# SWR_Tandem_Match.net
KiCad netlist of a schematic drawn in Altium Designer
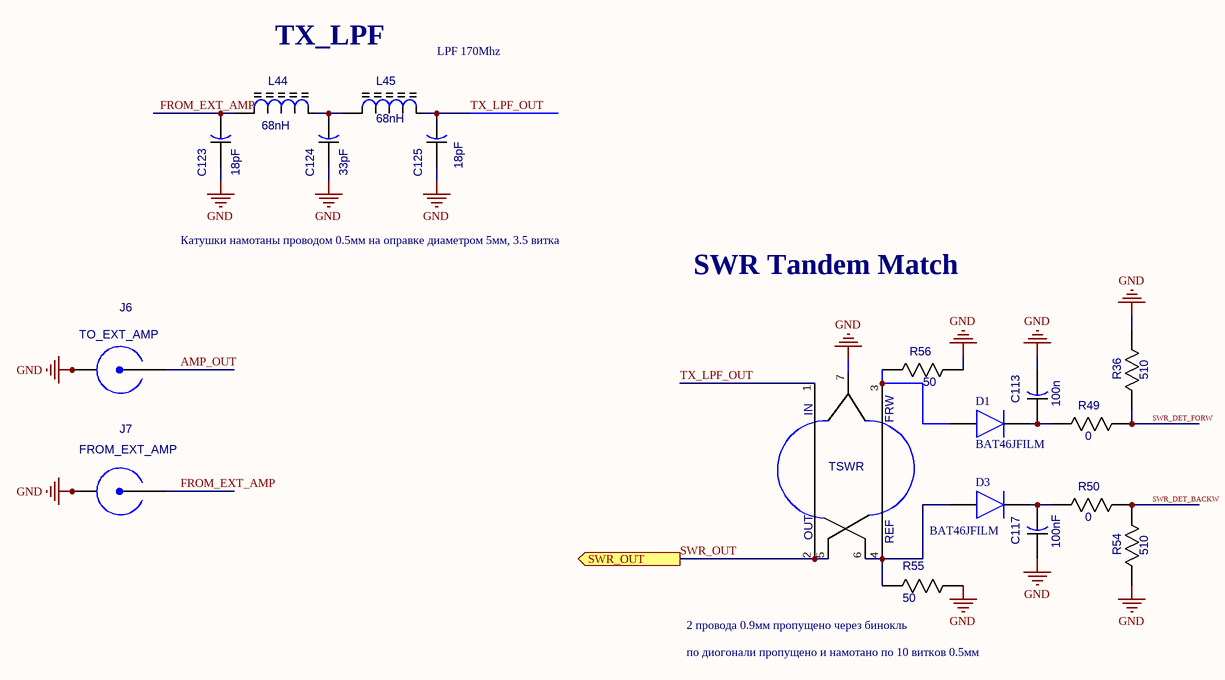
[diagram p0: SWR Tandem Match.SchDoc]

(export (version "E")
  (design (tool "Eeschema 10.0.6"))
  (components
    (comp (ref "C113")
      (value "100n")
      (footprint "CAP_0805")
      (description "CAP_0805")
      (libsource (lib "*") (part "CAP_0805"))
    )
    (comp (ref "C117")
      (value "100nF")
      (footprint "CAP_0805")
      (description "CAP_0805")
      (libsource (lib "*") (part "CAP_0805"))
    )
    (comp (ref "C123")
      (value "18pF")
      (footprint "CAP_1206")
      (description "CAP_1206")
      (libsource (lib "*") (part "CAP_1206"))
    )
    (comp (ref "C124")
      (value "33pF")
      (footprint "CAP_1206")
      (description "CAP_1206")
      (libsource (lib "*") (part "CAP_1206"))
    )
    (comp (ref "C125")
      (value "18pF")
      (footprint "CAP_1206")
      (description "CAP_1206")
      (libsource (lib "*") (part "CAP_1206"))
    )
    (comp (ref "D1")
      (value "BAT46JFILM")
      (footprint "SamacSys:SOD2513X117N")
      (description "Diode")
      (fields (field (name "MOUSER PART NUMBER") "511-BAT46JFILM") (field (name "RS PART NUMBER") "7146847P"))
      (libsource (lib "*") (part "BAT46JFILM"))
    )
    (comp (ref "D3")
      (value "BAT46JFILM")
      (footprint "SamacSys:SOD2513X117N")
      (description "Diode")
      (fields (field (name "MOUSER PART NUMBER") "511-BAT46JFILM") (field (name "RS PART NUMBER") "7146847P"))
      (libsource (lib "*") (part "BAT46JFILM"))
    )
    (comp (ref "J6")
      (value "TO_EXT_AMP")
      (footprint "31-5431")
      (description "SMA")
      (libsource (lib "RF-UNIT_1") (part "31-5431"))
    )
    (comp (ref "J7")
      (value "FROM_EXT_AMP")
      (footprint "31-5431")
      (description "SMA")
      (libsource (lib "RF-UNIT_1") (part "31-5431"))
    )
    (comp (ref "L44")
      (value "68nH")
      (footprint "IND_FERRITE_CORE_1")
      (description "Inductor")
      (libsource (lib "*") (part "IND_FERRITE_CORE"))
    )
    (comp (ref "L45")
      (value "68nH")
      (footprint "IND_FERRITE_CORE_1")
      (description "Inductor")
      (libsource (lib "*") (part "IND_FERRITE_CORE"))
    )
    (comp (ref "R36")
      (value "510")
      (footprint "RES_0805")
      (description "RES_0805")
      (libsource (lib "*") (part "RES_0805"))
    )
    (comp (ref "R49")
      (value "0")
      (footprint "RES_0805")
      (description "RES_0805")
      (libsource (lib "*") (part "RES_0805"))
    )
    (comp (ref "R50")
      (value "0")
      (footprint "RES_0805")
      (description "RES_0805")
      (libsource (lib "*") (part "RES_0805"))
    )
    (comp (ref "R54")
      (value "510")
      (footprint "RES_0805")
      (description "RES_0805")
      (libsource (lib "*") (part "RES_0805"))
    )
    (comp (ref "R55")
      (value "50")
      (footprint "RES_1206")
      (description "RES_1206")
      (libsource (lib "*") (part "RES_1206"))
    )
    (comp (ref "R56")
      (value "50")
      (footprint "RES_1206")
      (description "RES_1206")
      (libsource (lib "*") (part "RES_1206"))
    )
    (comp (ref "TSWR")
      (value "SWR_TANDEM_MATCH")
      (footprint "SWR_TANDEM_MATCH")
      (libsource (lib "*") (part "SWR_TANDEM_MATCH"))
    )
  )
  (nets
    (net (code "1") (name "/AMP_OUT") (class "Default")
      (node (ref "J6") (pin "5") (pinfunction "CON_5") (pintype "passive"))
    )
    (net (code "2") (name "/FROM_EXT_AMP") (class "Default")
      (node (ref "C123") (pin "2") (pinfunction "2_2") (pintype "passive"))
      (node (ref "J7") (pin "5") (pinfunction "CON_5") (pintype "passive"))
      (node (ref "L44") (pin "1") (pinfunction "A_1") (pintype "passive"))
    )
    (net (code "3") (name "/SWR_DET_BACKW") (class "Default")
      (node (ref "R50") (pin "2") (pinfunction "2_2") (pintype "passive"))
      (node (ref "R54") (pin "2") (pinfunction "2_2") (pintype "passive"))
    )
    (net (code "4") (name "/SWR_DET_FORW") (class "Default")
      (node (ref "R36") (pin "1") (pinfunction "1_1") (pintype "passive"))
      (node (ref "R49") (pin "2") (pinfunction "2_2") (pintype "passive"))
    )
    (net (code "5") (name "/SWR_OUT") (class "Default")
      (node (ref "TSWR") (pin "2") (pinfunction "2_2") (pintype "passive"))
      (node (ref "TSWR") (pin "5") (pinfunction "5_5") (pintype "passive"))
    )
    (net (code "6") (name "/TX_LPF_OUT") (class "Default")
      (node (ref "C125") (pin "2") (pinfunction "2_2") (pintype "passive"))
      (node (ref "L45") (pin "2") (pinfunction "B_2") (pintype "passive"))
      (node (ref "TSWR") (pin "1") (pinfunction "1_1") (pintype "passive"))
    )
    (net (code "7") (name "GND") (class "Default")
      (node (ref "C113") (pin "2") (pinfunction "2_2") (pintype "passive"))
      (node (ref "C117") (pin "1") (pinfunction "1_1") (pintype "passive"))
      (node (ref "C123") (pin "1") (pinfunction "1_1") (pintype "passive"))
      (node (ref "C124") (pin "1") (pinfunction "1_1") (pintype "passive"))
      (node (ref "C125") (pin "1") (pinfunction "1_1") (pintype "passive"))
      (node (ref "J6") (pin "1") (pinfunction "GND_1") (pintype "passive"))
      (node (ref "J6") (pin "2") (pinfunction "GND_2") (pintype "passive"))
      (node (ref "J6") (pin "3") (pinfunction "GND_3") (pintype "passive"))
      (node (ref "J6") (pin "4") (pinfunction "GND_4") (pintype "passive"))
      (node (ref "J7") (pin "1") (pinfunction "GND_1") (pintype "passive"))
      (node (ref "J7") (pin "2") (pinfunction "GND_2") (pintype "passive"))
      (node (ref "J7") (pin "3") (pinfunction "GND_3") (pintype "passive"))
      (node (ref "J7") (pin "4") (pinfunction "GND_4") (pintype "passive"))
      (node (ref "R36") (pin "2") (pinfunction "2_2") (pintype "passive"))
      (node (ref "R54") (pin "1") (pinfunction "1_1") (pintype "passive"))
      (node (ref "R55") (pin "2") (pinfunction "2_2") (pintype "passive"))
      (node (ref "R56") (pin "2") (pinfunction "2_2") (pintype "passive"))
      (node (ref "TSWR") (pin "7") (pinfunction "7_7") (pintype "passive"))
    )
    (net (code "8") (name "Net-(D1-A)") (class "Default")
      (node (ref "D1") (pin "2") (pinfunction "A_2") (pintype "passive"))
      (node (ref "R56") (pin "1") (pinfunction "1_1") (pintype "passive"))
      (node (ref "TSWR") (pin "3") (pinfunction "3_3") (pintype "passive"))
    )
    (net (code "9") (name "Net-(D1-K)") (class "Default")
      (node (ref "C113") (pin "1") (pinfunction "1_1") (pintype "passive"))
      (node (ref "D1") (pin "1") (pinfunction "K_1") (pintype "passive"))
      (node (ref "R49") (pin "1") (pinfunction "1_1") (pintype "passive"))
    )
    (net (code "10") (name "Net-(D3-A)") (class "Default")
      (node (ref "D3") (pin "2") (pinfunction "A_2") (pintype "passive"))
      (node (ref "R55") (pin "1") (pinfunction "1_1") (pintype "passive"))
      (node (ref "TSWR") (pin "4") (pinfunction "4_4") (pintype "passive"))
      (node (ref "TSWR") (pin "6") (pinfunction "6_6") (pintype "passive"))
    )
    (net (code "11") (name "Net-(D3-K)") (class "Default")
      (node (ref "C117") (pin "2") (pinfunction "2_2") (pintype "passive"))
      (node (ref "D3") (pin "1") (pinfunction "K_1") (pintype "passive"))
      (node (ref "R50") (pin "1") (pinfunction "1_1") (pintype "passive"))
    )
    (net (code "12") (name "Net-(L44-B)") (class "Default")
      (node (ref "C124") (pin "2") (pinfunction "2_2") (pintype "passive"))
      (node (ref "L44") (pin "2") (pinfunction "B_2") (pintype "passive"))
      (node (ref "L45") (pin "1") (pinfunction "A_1") (pintype "passive"))
    )
  )
)
